# SD_proto.net
KiCad netlist of a schematic drawn in Altium Designer
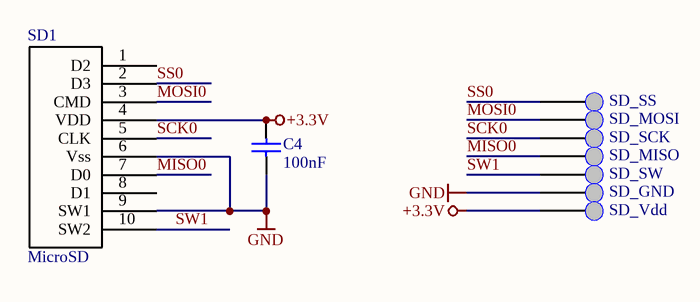
[diagram p0: SD_proto.SchDoc]

(export (version "E")
  (design (tool "Eeschema 10.0.6"))
  (components
    (comp (ref "C4")
      (value "100nF")
      (footprint "0603")
      (description "Ceramic Chip Capacitor - Standard")
      (fields (field (name "Comment") "C0603") (field (name "PUBLISHER") "Altium Limited"))
      (libsource (lib "KEMET Chip Capacitor") (part "C0603"))
    )
    (comp (ref "SD1") (value "MicroSD") (footprint "micro SD") (libsource (lib "moja") (part "MicroSD")))
    (comp (ref "SD_GND")
      (value "Testpoint")
      (footprint "En_pin_TP")
      (libsource (lib "moja") (part "Testpoint"))
    )
    (comp (ref "SD_MISO")
      (value "Testpoint")
      (footprint "En_pin_TP")
      (libsource (lib "moja") (part "Testpoint"))
    )
    (comp (ref "SD_MOSI")
      (value "Testpoint")
      (footprint "En_pin_TP")
      (libsource (lib "moja") (part "Testpoint"))
    )
    (comp (ref "SD_SCK")
      (value "Testpoint")
      (footprint "En_pin_TP")
      (libsource (lib "moja") (part "Testpoint"))
    )
    (comp (ref "SD_SS")
      (value "Testpoint")
      (footprint "En_pin_TP")
      (libsource (lib "moja") (part "Testpoint"))
    )
    (comp (ref "SD_SW")
      (value "Testpoint")
      (footprint "En_pin_TP")
      (libsource (lib "moja") (part "Testpoint"))
    )
    (comp (ref "SD_Vdd")
      (value "Testpoint")
      (footprint "En_pin_TP")
      (libsource (lib "moja") (part "Testpoint"))
    )
  )
  (nets
    (net (code "1") (name "+3.3V") (class "Default")
      (node (ref "C4") (pin "1") (pinfunction "1_1") (pintype "passive"))
      (node (ref "SD1") (pin "4") (pinfunction "VDD_4") (pintype "passive"))
      (node (ref "SD_Vdd") (pin "1") (pinfunction "1_1") (pintype "passive"))
    )
    (net (code "2") (name "/MISO0") (class "Default")
      (node (ref "SD1") (pin "7") (pinfunction "D0_7") (pintype "passive"))
      (node (ref "SD_MISO") (pin "1") (pinfunction "1_1") (pintype "passive"))
    )
    (net (code "3") (name "/MOSI0") (class "Default")
      (node (ref "SD1") (pin "3") (pinfunction "CMD_3") (pintype "passive"))
      (node (ref "SD_MOSI") (pin "1") (pinfunction "1_1") (pintype "passive"))
    )
    (net (code "4") (name "/SCK0") (class "Default")
      (node (ref "SD1") (pin "5") (pinfunction "CLK_5") (pintype "passive"))
      (node (ref "SD_SCK") (pin "1") (pinfunction "1_1") (pintype "passive"))
    )
    (net (code "5") (name "/SS0") (class "Default")
      (node (ref "SD1") (pin "2") (pinfunction "D3_2") (pintype "passive"))
      (node (ref "SD_SS") (pin "1") (pinfunction "1_1") (pintype "passive"))
    )
    (net (code "6") (name "/SW1") (class "Default")
      (node (ref "SD1") (pin "10") (pinfunction "SW2_10") (pintype "passive"))
      (node (ref "SD_SW") (pin "1") (pinfunction "1_1") (pintype "passive"))
    )
    (net (code "7") (name "GND") (class "Default")
      (node (ref "C4") (pin "2") (pinfunction "2_2") (pintype "passive"))
      (node (ref "SD1") (pin "6") (pinfunction "Vss_6") (pintype "passive"))
      (node (ref "SD1") (pin "9") (pinfunction "SW1_9") (pintype "passive"))
      (node (ref "SD_GND") (pin "1") (pinfunction "1_1") (pintype "passive"))
    )
    (net (code "8") (name "unconnected-(SD1-D1-Pad8)") (class "Default")
      (node (ref "SD1") (pin "8") (pinfunction "D1_8") (pintype "passive"))
    )
    (net (code "9") (name "unconnected-(SD1-D2-Pad1)") (class "Default")
      (node (ref "SD1") (pin "1") (pinfunction "D2_1") (pintype "passive"))
    )
  )
)
